# Motor_Driver.net
KiCad netlist of a schematic drawn in Altium Designer
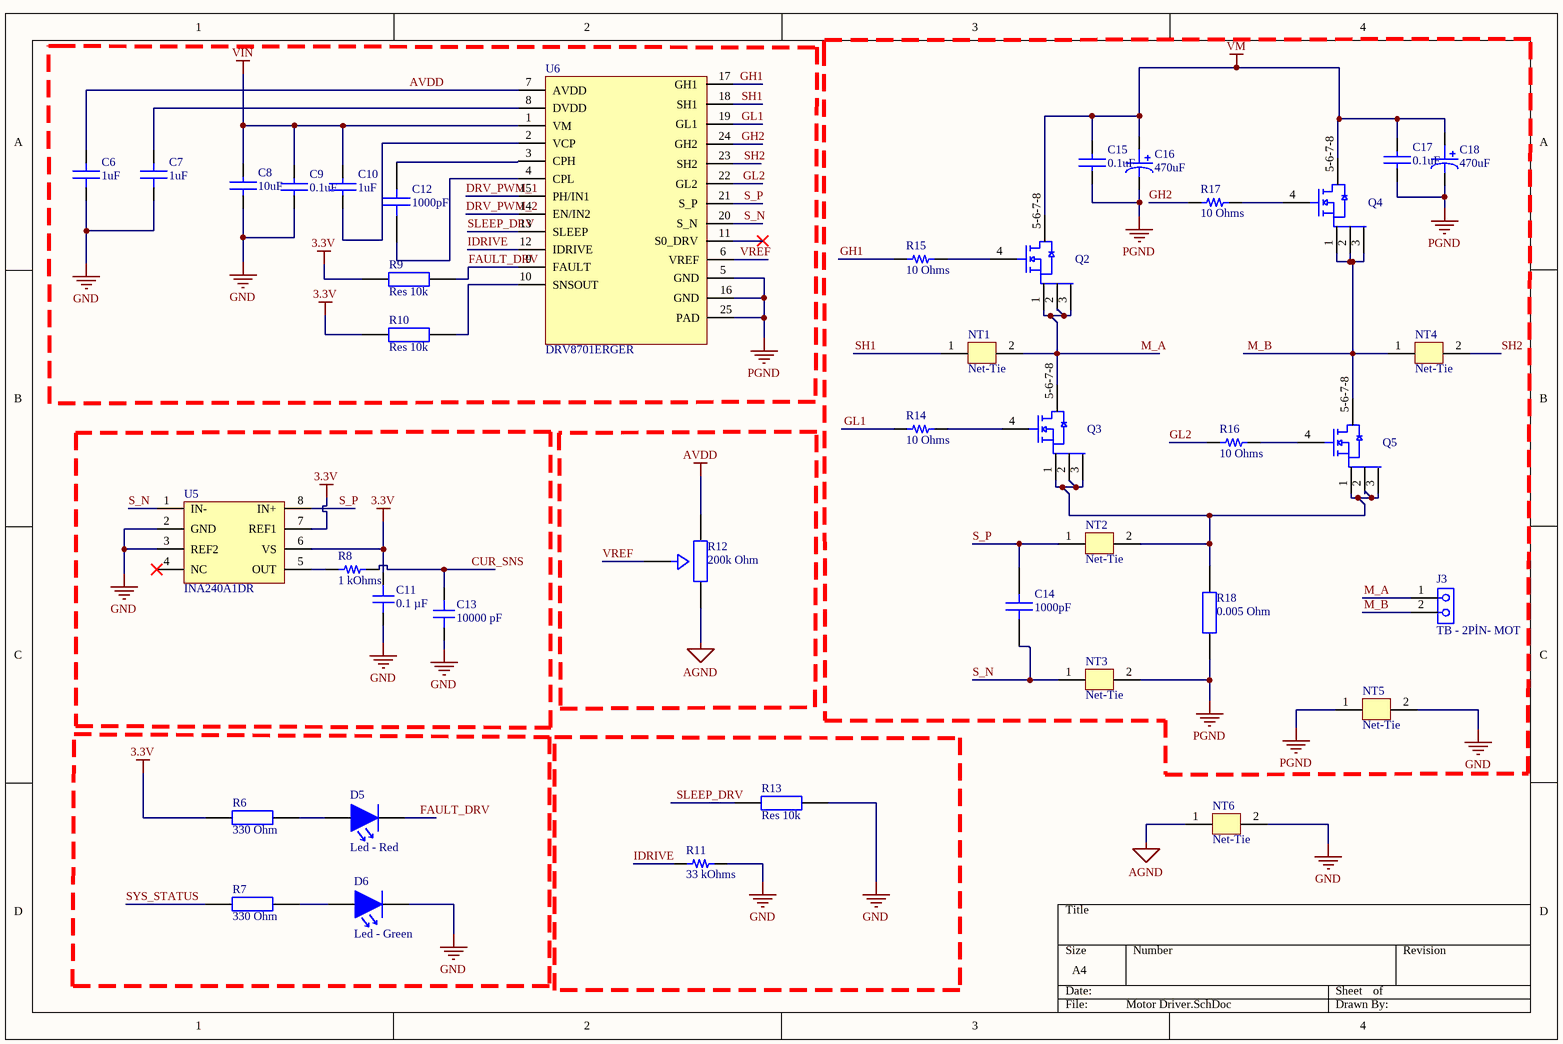
[diagram p0: Motor Driver.SchDoc]

(export (version "E")
  (design (tool "Eeschema 10.0.6"))
  (components
    (comp (ref "C6")
      (value "1uF")
      (footprint "CAP0603-GRM188R60J105KA01D")
      (description "0603 1 uF 6.3 V ±10% Tolerance X5R SMT Multilayer Ceramic Capacitor")
      (fields
        (field (name "MANUFACTURER") "Murata")
        (field (name "MANUFACTURER PART NUMBER") "GRM188R60J105KA01D")
      )
      (libsource (lib "TIDA_00620") (part "GRM188R60J105KA01D"))
    )
    (comp (ref "C7")
      (value "1uF")
      (footprint "CAP0603-GRM188R60J105KA01D")
      (description "0603 1 uF 6.3 V ±10% Tolerance X5R SMT Multilayer Ceramic Capacitor")
      (fields
        (field (name "MANUFACTURER") "Murata")
        (field (name "MANUFACTURER PART NUMBER") "GRM188R60J105KA01D")
      )
      (libsource (lib "TIDA_00620") (part "GRM188R60J105KA01D"))
    )
    (comp (ref "C8")
      (value "10uF")
      (footprint "CAP1210- GRM32ER71H106KA12L")
      (description "50V 10uF X7R ±10% 1210 Multilayer Ceramic Capacitors MLCC - SMD/SMT ROHS")
      (fields
        (field (name "MANUFACTURER") "Murata")
        (field (name "MANUFACTURER PART NUMBER") "GRM32ER71H106KA12L")
      )
      (libsource (lib "TIDA_00620") (part "GRM32ER71H106KA12L"))
    )
    (comp (ref "C9")
      (value "0.1uF")
      (footprint "CAP1206- GRM319R71H104KA01D")
      (description "1206 0.1 uF 50 V ±10 % Tolerance X7R Surface Mount Multilayer Ceramic Capacitor")
      (fields
        (field (name "MANUFACTURER") "Murata")
        (field (name "MANUFACTURER PART NUMBER") "GRM319R71H104KA01D")
      )
      (libsource (lib "TIDA_00620") (part "GRM319R71H104KA01D"))
    )
    (comp (ref "C10")
      (value "1uF")
      (footprint "CAP1206- GRM319R71C105KAA3D")
      (description "1206 1 uF 16 V ±10 % Tol. X7R Surface Mount Multilayer Ceramic Capacitor")
      (fields
        (field (name "MANUFACTURER") "Murata")
        (field (name "MANUFACTURER PART NUMBER") "GRM319R71C105KAA3D")
      )
      (libsource (lib "TIDA_00620") (part "GRM319R71C105KAA3D"))
    )
    (comp (ref "C11")
      (value "0.1 µF")
      (footprint "CAP 0603_1608")
      (description "CAP CER 0.1UF 16V X7R 0603")
      (fields
        (field (name "PART NUMBER") "AC0603KPX7R7BB104")
        (field (name "CAPACITANCE") "0.1 µF")
        (field (name "MANUFACTURER") "Yageo")
      )
      (libsource (lib "Celestial Altium Library - altium_library") (part "Capacitor"))
    )
    (comp (ref "C12")
      (value "1000pF")
      (footprint "CAP0402- GRM155R71C102KA01D")
      (description "0402 1 nF 16 V ±10% Tolerance X7R SMT Multilayer Ceramic Capacitor")
      (fields
        (field (name "MANUFACTURER") "Murata")
        (field (name "MANUFACTURER PART NUMBER") "GRM155R71C102KA01D")
      )
      (libsource (lib "") (part "GRM155R71C102KA01D_1"))
    )
    (comp (ref "C13")
      (value "10000 pF")
      (footprint "CAP 0402_1005")
      (description "CAP CER 0402 10NF 100VDC X7R")
      (fields
        (field (name "PART NUMBER") "C0402C103K1RACTU")
        (field (name "CAPACITANCE") "10000 pF")
        (field (name "MANUFACTURER") "KEMET")
      )
      (libsource (lib "Celestial Altium Library - altium_library") (part "Capacitor"))
    )
    (comp (ref "C14")
      (value "1000pF")
      (footprint "CAP0402- GRM155R71C102KA01D")
      (description "0402 1 nF 16 V ±10% Tolerance X7R SMT Multilayer Ceramic Capacitor")
      (fields
        (field (name "MANUFACTURER") "Murata")
        (field (name "MANUFACTURER PART NUMBER") "GRM155R71C102KA01D")
      )
      (libsource (lib "TIDA_00620") (part "GRM155R71C102KA01D"))
    )
    (comp (ref "C15")
      (value "0.1uF")
      (footprint "CAP1206- GRM319R71H104KA01D")
      (description "1206 0.1 uF 50 V ±10 % Tolerance X7R Surface Mount Multilayer Ceramic Capacitor")
      (fields
        (field (name "MANUFACTURER") "Murata")
        (field (name "MANUFACTURER PART NUMBER") "GRM319R71H104KA01D")
      )
      (libsource (lib "TIDA_00620") (part "GRM319R71H104KA01D"))
    )
    (comp (ref "C16")
      (value "470uF")
      (footprint "RCAP, 8x20mm -EEU-FR1V471LB")
      (description "Aluminum Electrolytic Capacitor, Polarized, Aluminum (wet), 25V, 20% +Tol, 20% -Tol, 560uF")
      (fields
        (field (name "MANUFACTURER") "Panasonic")
        (field (name "MANUFACTURER PART NUMBER") "EEU-FR1V471LB")
      )
      (libsource (lib "TIDA_00620") (part "EEU-FR1V471LB"))
    )
    (comp (ref "C17")
      (value "0.1uF")
      (footprint "CAP1206- GRM319R71H104KA01D")
      (description "1206 0.1 uF 50 V ±10 % Tolerance X7R Surface Mount Multilayer Ceramic Capacitor")
      (fields
        (field (name "MANUFACTURER") "Murata")
        (field (name "MANUFACTURER PART NUMBER") "GRM319R71H104KA01D")
      )
      (libsource (lib "TIDA_00620") (part "GRM319R71H104KA01D"))
    )
    (comp (ref "C18")
      (value "470uF")
      (footprint "RCAP, 8x20mm -EEU-FR1V471LB")
      (description "Aluminum Electrolytic Capacitor, Polarized, Aluminum (wet), 25V, 20% +Tol, 20% -Tol, 560uF")
      (fields
        (field (name "MANUFACTURER") "Panasonic")
        (field (name "MANUFACTURER PART NUMBER") "EEU-FR1V471LB")
      )
      (libsource (lib "TIDA_00620") (part "EEU-FR1V471LB"))
    )
    (comp (ref "D5")
      (value "Led - Red")
      (footprint "LED_0805")
      (description "Single-color LEDs; LITEON; LTST-C170KRKT; Red; 130 °; 2 V; 0805")
      (fields
        (field (name "MANUFACTURER") "Lite-On")
        (field (name "MANUFACTURER PART NUMBER") "LTST-C170KRKT")
        (field (name "DESIGNED") "Emre")
      )
      (libsource (lib "TIDA_00620") (part "LTST-C170KRKT"))
    )
    (comp (ref "D6")
      (value "Led - Green")
      (footprint "LED_0805")
      (description "LED Low-Power Uni-Color Green 565nm 2.1V 2-Pin Chip LED T/R")
      (fields
        (field (name "MANUFACTURER") "Lite-On")
        (field (name "MANUFACTURER PART NUMBER") "LTST-C171GKT")
        (field (name "DESIGNED") "Emre")
      )
      (libsource (lib "TIDA_00620") (part "LTST-C171GKT"))
    )
    (comp (ref "J3")
      (value "TB - 2PİN- MOT")
      (footprint "TB - 2PİN- MOT")
      (libsource (lib "TIDA_00620") (part "TB - 2PİN- MOT"))
    )
    (comp (ref "NT1") (value "Net-Tie") (footprint "Net-Tie") (libsource (lib "TIDA_00620") (part "Net-Tie")))
    (comp (ref "NT2") (value "Net-Tie") (footprint "Net-Tie") (libsource (lib "TIDA_00620") (part "Net-Tie")))
    (comp (ref "NT3") (value "Net-Tie") (footprint "Net-Tie") (libsource (lib "TIDA_00620") (part "Net-Tie")))
    (comp (ref "NT4") (value "Net-Tie") (footprint "Net-Tie") (libsource (lib "TIDA_00620") (part "Net-Tie")))
    (comp (ref "NT5") (value "Net-Tie") (footprint "Net-Tie") (libsource (lib "TIDA_00620") (part "Net-Tie")))
    (comp (ref "NT6") (value "Net-Tie") (footprint "Net-Tie") (libsource (lib "TIDA_00620") (part "Net-Tie")))
    (comp (ref "Q2")
      (value "BSC010N04LSI")
      (footprint "SON 5X6")
      (description "Transistor: N-MOSFET; unipolar; 40V; 100A; 139W; PG-TDSON-8")
      (fields
        (field (name "MANUFACTURER") "Infineon")
        (field (name "MANUFACTURER PART NUMBER") "BSC010N04LSIATMA1")
      )
      (libsource (lib "UAV") (part "BSC010N04LSI"))
    )
    (comp (ref "Q3")
      (value "BSC010N04LSI")
      (footprint "SON 5X6")
      (description "Transistor: N-MOSFET; unipolar; 40V; 100A; 139W; PG-TDSON-8")
      (fields
        (field (name "MANUFACTURER") "Infineon")
        (field (name "MANUFACTURER PART NUMBER") "BSC010N04LSIATMA1")
      )
      (libsource (lib "UAV") (part "BSC010N04LSI"))
    )
    (comp (ref "Q4")
      (value "BSC010N04LSI")
      (footprint "SON 5X6")
      (description "Transistor: N-MOSFET; unipolar; 40V; 100A; 139W; PG-TDSON-8")
      (fields
        (field (name "MANUFACTURER") "Infineon")
        (field (name "MANUFACTURER PART NUMBER") "BSC010N04LSIATMA1")
      )
      (libsource (lib "UAV") (part "BSC010N04LSI"))
    )
    (comp (ref "Q5")
      (value "BSC010N04LSI")
      (footprint "SON 5X6")
      (description "Transistor: N-MOSFET; unipolar; 40V; 100A; 139W; PG-TDSON-8")
      (fields
        (field (name "MANUFACTURER") "Infineon")
        (field (name "MANUFACTURER PART NUMBER") "BSC010N04LSIATMA1")
      )
      (libsource (lib "UAV") (part "BSC010N04LSI"))
    )
    (comp (ref "R6")
      (value "330 Ohm")
      (footprint "RES0603- RC0603FR-07330RL")
      (description "Res Thick Film 0603 330 Ohm 1% 0.1W(1/10W) ±100ppm/C Pad SMD T/R")
      (fields
        (field (name "MANUFACTURER") "Yageo Group")
        (field (name "MANUFACTURER PART NUMBER") "RC0603FR-07330RL")
      )
      (libsource (lib "TIDA_00620") (part "RC0603FR-07330RL"))
    )
    (comp (ref "R7")
      (value "330 Ohm")
      (footprint "RES0603- RC0603FR-07330RL")
      (description "Res Thick Film 0603 330 Ohm 1% 0.1W(1/10W) ±100ppm/C Pad SMD T/R")
      (fields
        (field (name "MANUFACTURER") "Yageo Group")
        (field (name "MANUFACTURER PART NUMBER") "RC0603FR-07330RL")
      )
      (libsource (lib "TIDA_00620") (part "RC0603FR-07330RL"))
    )
    (comp (ref "R8")
      (value "1 kOhms")
      (footprint "RES 0603_1608")
      (description "RES SMD 1K OHM 5% 1/4W 0603")
      (fields (field (name "PART NUMBER") "ESR03EZPJ102") (field (name "MANUFACTURER") "Rohm Semiconductor"))
      (libsource (lib "Celestial Altium Library - altium_library") (part "Resistor"))
    )
    (comp (ref "R9")
      (value "Res 10k")
      (footprint "RES0402 - ERJ-2RKF1002X")
      (description "Res Thick Film 0402 10K Ohm 1% 1/10W ±100ppm/°C Molded SMD Punched Carrier T/R")
      (fields
        (field (name "MANUFACTURER") "Panasonic")
        (field (name "MANUFACTURER PART NUMBER") "ERJ-2RKF1002X")
      )
      (libsource (lib "TIDA_00620") (part "ERJ-2RKF1002X"))
    )
    (comp (ref "R10")
      (value "Res 10k")
      (footprint "RES0402 - ERJ-2RKF1002X")
      (description "Res Thick Film 0402 10K Ohm 1% 1/10W ±100ppm/°C Molded SMD Punched Carrier T/R")
      (fields
        (field (name "MANUFACTURER") "Panasonic")
        (field (name "MANUFACTURER PART NUMBER") "ERJ-2RKF1002X")
      )
      (libsource (lib "TIDA_00620") (part "ERJ-2RKF1002X"))
    )
    (comp (ref "R11")
      (value "33 kOhms")
      (footprint "RES 1206_3216")
      (description "RES SMD 33K OHM 0.05% 1/4W 1206")
      (fields
        (field (name "PART NUMBER") "ERA-8ARW333V")
        (field (name "MANUFACTURER") "Panasonic Electronic Components")
      )
      (libsource (lib "Celestial Altium Library - altium_library") (part "Resistor"))
    )
    (comp (ref "R12")
      (value "200k Ohm")
      (footprint "3352P-1-204LF")
      (description "Res Cermet Trimmer 200K Ohm 20% 1/2W 1(Elec)/1(Mech)Turn (8.89 X 10.67 X 5.33mm) Pin Thru-Hole Bag")
      (fields
        (field (name "MANUFACTURER") "Bourns")
        (field (name "MANUFACTURER PART NUMBER") "3352P-1-204LF")
      )
      (libsource (lib "TIDA_00620") (part "3352P-1-204LF"))
    )
    (comp (ref "R13")
      (value "Res 10k")
      (footprint "RES0402 - ERJ-2RKF1002X")
      (description "Res Thick Film 0402 10K Ohm 1% 1/10W ±100ppm/°C Molded SMD Punched Carrier T/R")
      (fields
        (field (name "MANUFACTURER") "Panasonic")
        (field (name "MANUFACTURER PART NUMBER") "ERJ-2RKF1002X")
      )
      (libsource (lib "TIDA_00620") (part "ERJ-2RKF1002X"))
    )
    (comp (ref "R14")
      (value "10 Ohms")
      (footprint "RES 0805_2012")
      (description "RES SMD 10 OHM 0.5% 1/4W 0805")
      (fields
        (field (name "PART NUMBER") "RNCF0805DTE10R0")
        (field (name "MANUFACTURER") "Stackpole Electronics Inc")
      )
      (libsource (lib "Celestial Altium Library - altium_library") (part "Resistor"))
    )
    (comp (ref "R15")
      (value "10 Ohms")
      (footprint "RES 0805_2012")
      (description "RES SMD 10 OHM 0.5% 1/4W 0805")
      (fields
        (field (name "PART NUMBER") "RNCF0805DTE10R0")
        (field (name "MANUFACTURER") "Stackpole Electronics Inc")
      )
      (libsource (lib "Celestial Altium Library - altium_library") (part "Resistor"))
    )
    (comp (ref "R16")
      (value "10 Ohms")
      (footprint "RES 0805_2012")
      (description "RES SMD 10 OHM 0.5% 1/4W 0805")
      (fields
        (field (name "PART NUMBER") "RNCF0805DTE10R0")
        (field (name "MANUFACTURER") "Stackpole Electronics Inc")
      )
      (libsource (lib "Celestial Altium Library - altium_library") (part "Resistor"))
    )
    (comp (ref "R17")
      (value "10 Ohms")
      (footprint "RES 0805_2012")
      (description "RES SMD 10 OHM 0.5% 1/4W 0805")
      (fields
        (field (name "PART NUMBER") "RNCF0805DTE10R0")
        (field (name "MANUFACTURER") "Stackpole Electronics Inc")
      )
      (libsource (lib "Celestial Altium Library - altium_library") (part "Resistor"))
    )
    (comp (ref "R18")
      (value "0.005 Ohm")
      (footprint "KRL11050-C-R005-F-T1")
      (description "Fixed Resistor, Metal Foil, 5W, 0.005ohm, 1% +/-Tol, 50ppm/Cel, Surface Mount, 4320")
      (fields
        (field (name "MANUFACTURER") "Susumu")
        (field (name "MANUFACTURER PART NUMBER") "KRL11050-C-R005-F-T1")
      )
      (libsource (lib "TIDA_00620") (part "KRL11050-C-R005-F-T1"))
    )
    (comp (ref "U5")
      (value "INA240A1DR")
      (footprint "INA240A1DR")
      (description "Op Amp Single Zero Drift Amplifier 5.5V 8-Pin SOIC T/R")
      (fields (field (name "MANUFACTURER") "Texas Instruments"))
      (libsource (lib "TIDA_00620") (part "INA240A1DR"))
    )
    (comp (ref "U6")
      (value "DRV8701ERGER")
      (footprint "DRV8701ERGER")
      (description "IC MOTOR DRIVER 0V-5.5V 24VQFN / DRV8701 Brushed DC Motor Full-Bridge Gate Driver")
      (fields (field (name "MANUFACTURER") "Texas Instruments"))
      (libsource (lib "TIDA_00620") (part "DRV8701ERGER"))
    )
  )
  (nets
    (net (code "1") (name "/CUR_SNS") (class "Default")
      (node (ref "C13") (pin "2") (pinfunction "2_2") (pintype "passive"))
      (node (ref "R8") (pin "2") (pinfunction "2_2") (pintype "passive"))
    )
    (net (code "2") (name "/DRV_PWM_1") (class "Default")
      (node (ref "U6") (pin "15") (pinfunction "PH/IN1_15") (pintype "passive"))
    )
    (net (code "3") (name "/DRV_PWM_2") (class "Default")
      (node (ref "U6") (pin "14") (pinfunction "EN/IN2_14") (pintype "passive"))
    )
    (net (code "4") (name "/FAULT_DRV") (class "Default")
      (node (ref "D5") (pin "1") (pinfunction "1_1") (pintype "power_in"))
      (node (ref "R9") (pin "2") (pinfunction "2_2") (pintype "passive"))
      (node (ref "U6") (pin "9") (pinfunction "FAULT_9") (pintype "passive"))
    )
    (net (code "5") (name "/GH1") (class "Default")
      (node (ref "R15") (pin "1") (pinfunction "1_1") (pintype "passive"))
      (node (ref "U6") (pin "17") (pinfunction "GH1_17") (pintype "passive"))
    )
    (net (code "6") (name "/GH2") (class "Default")
      (node (ref "R17") (pin "1") (pinfunction "1_1") (pintype "passive"))
      (node (ref "U6") (pin "24") (pinfunction "GH2_24") (pintype "passive"))
    )
    (net (code "7") (name "/GL1") (class "Default")
      (node (ref "R14") (pin "1") (pinfunction "1_1") (pintype "passive"))
      (node (ref "U6") (pin "19") (pinfunction "GL1_19") (pintype "passive"))
    )
    (net (code "8") (name "/GL2") (class "Default")
      (node (ref "R16") (pin "1") (pinfunction "1_1") (pintype "passive"))
      (node (ref "U6") (pin "22") (pinfunction "GL2_22") (pintype "passive"))
    )
    (net (code "9") (name "/IDRIVE") (class "Default")
      (node (ref "R11") (pin "2") (pinfunction "2_2") (pintype "passive"))
      (node (ref "U6") (pin "12") (pinfunction "IDRIVE_12") (pintype "passive"))
    )
    (net (code "10") (name "/M_A") (class "Default")
      (node (ref "J3") (pin "1") (pinfunction "1_1") (pintype "passive"))
      (node (ref "NT1") (pin "2") (pinfunction "2_2") (pintype "passive"))
      (node (ref "Q2") (pin "1") (pinfunction "S_1") (pintype "passive"))
      (node (ref "Q2") (pin "2") (pinfunction "S_2") (pintype "passive"))
      (node (ref "Q2") (pin "3") (pinfunction "S_3") (pintype "passive"))
      (node (ref "Q3") (pin "5-6-7-8") (pinfunction "D_5-6-7-8") (pintype "passive"))
    )
    (net (code "11") (name "/M_B") (class "Default")
      (node (ref "J3") (pin "2") (pinfunction "2_2") (pintype "passive"))
      (node (ref "NT4") (pin "1") (pinfunction "1_1") (pintype "passive"))
      (node (ref "Q4") (pin "1") (pinfunction "S_1") (pintype "passive"))
      (node (ref "Q4") (pin "2") (pinfunction "S_2") (pintype "passive"))
      (node (ref "Q4") (pin "3") (pinfunction "S_3") (pintype "passive"))
      (node (ref "Q5") (pin "5-6-7-8") (pinfunction "D_5-6-7-8") (pintype "passive"))
    )
    (net (code "12") (name "/SH1") (class "Default")
      (node (ref "NT1") (pin "1") (pinfunction "1_1") (pintype "passive"))
      (node (ref "U6") (pin "18") (pinfunction "SH1_18") (pintype "passive"))
    )
    (net (code "13") (name "/SH2") (class "Default")
      (node (ref "NT4") (pin "2") (pinfunction "2_2") (pintype "passive"))
      (node (ref "U6") (pin "23") (pinfunction "SH2_23") (pintype "passive"))
    )
    (net (code "14") (name "/SLEEP_DRV") (class "Default")
      (node (ref "R13") (pin "1") (pinfunction "1_1") (pintype "passive"))
      (node (ref "U6") (pin "13") (pinfunction "SLEEP_13") (pintype "passive"))
    )
    (net (code "15") (name "/SYS_STATUS") (class "Default")
      (node (ref "R7") (pin "1") (pinfunction "1_1") (pintype "passive"))
    )
    (net (code "16") (name "/S_N") (class "Default")
      (node (ref "C14") (pin "1") (pinfunction "1_1") (pintype "passive"))
      (node (ref "NT3") (pin "1") (pinfunction "1_1") (pintype "passive"))
      (node (ref "U5") (pin "1") (pinfunction "IN-_1") (pintype "passive"))
      (node (ref "U6") (pin "20") (pinfunction "S_N_20") (pintype "passive"))
    )
    (net (code "17") (name "/S_P") (class "Default")
      (node (ref "C14") (pin "2") (pinfunction "2_2") (pintype "passive"))
      (node (ref "NT2") (pin "1") (pinfunction "1_1") (pintype "passive"))
      (node (ref "U5") (pin "8") (pinfunction "IN+_8") (pintype "passive"))
      (node (ref "U6") (pin "21") (pinfunction "S_P_21") (pintype "passive"))
    )
    (net (code "18") (name "/VREF") (class "Default")
      (node (ref "R12") (pin "1") (pinfunction "1_1") (pintype "passive"))
      (node (ref "U6") (pin "6") (pinfunction "VREF_6") (pintype "passive"))
    )
    (net (code "19") (name "3.3V") (class "Default")
      (node (ref "C11") (pin "2") (pinfunction "2_2") (pintype "passive"))
      (node (ref "R10") (pin "1") (pinfunction "1_1") (pintype "passive"))
      (node (ref "R6") (pin "1") (pinfunction "1_1") (pintype "passive"))
      (node (ref "R9") (pin "1") (pinfunction "1_1") (pintype "passive"))
      (node (ref "U5") (pin "6") (pinfunction "VS_6") (pintype "passive"))
      (node (ref "U5") (pin "7") (pinfunction "REF1_7") (pintype "passive"))
    )
    (net (code "20") (name "AGND") (class "Default")
      (node (ref "NT6") (pin "1") (pinfunction "1_1") (pintype "passive"))
      (node (ref "R12") (pin "3") (pinfunction "3_3") (pintype "passive"))
    )
    (net (code "21") (name "AVDD") (class "Default")
      (node (ref "C6") (pin "2") (pinfunction "2_2") (pintype "passive"))
      (node (ref "R12") (pin "2") (pinfunction "2_2") (pintype "passive"))
      (node (ref "U6") (pin "7") (pinfunction "AVDD_7") (pintype "passive"))
    )
    (net (code "22") (name "GND") (class "Default")
      (node (ref "C11") (pin "1") (pinfunction "1_1") (pintype "passive"))
      (node (ref "C13") (pin "1") (pinfunction "1_1") (pintype "passive"))
      (node (ref "C6") (pin "1") (pinfunction "1_1") (pintype "passive"))
      (node (ref "C7") (pin "1") (pinfunction "1_1") (pintype "passive"))
      (node (ref "C8") (pin "1") (pinfunction "1_1") (pintype "passive"))
      (node (ref "C9") (pin "1") (pinfunction "1_1") (pintype "passive"))
      (node (ref "D6") (pin "1") (pinfunction "1_1") (pintype "power_in"))
      (node (ref "NT5") (pin "2") (pinfunction "2_2") (pintype "passive"))
      (node (ref "NT6") (pin "2") (pinfunction "2_2") (pintype "passive"))
      (node (ref "R11") (pin "1") (pinfunction "1_1") (pintype "passive"))
      (node (ref "R13") (pin "2") (pinfunction "2_2") (pintype "passive"))
      (node (ref "U5") (pin "2") (pinfunction "GND_2") (pintype "passive"))
      (node (ref "U5") (pin "3") (pinfunction "REF2_3") (pintype "passive"))
    )
    (net (code "23") (name "Net-(D5-Pad2)") (class "Default")
      (node (ref "D5") (pin "2") (pinfunction "2_2") (pintype "power_in"))
      (node (ref "R6") (pin "2") (pinfunction "2_2") (pintype "passive"))
    )
    (net (code "24") (name "Net-(D6-Pad2)") (class "Default")
      (node (ref "D6") (pin "2") (pinfunction "2_2") (pintype "power_in"))
      (node (ref "R7") (pin "2") (pinfunction "2_2") (pintype "passive"))
    )
    (net (code "25") (name "Net-(NT2-Pad2)") (class "Default")
      (node (ref "NT2") (pin "2") (pinfunction "2_2") (pintype "passive"))
      (node (ref "Q3") (pin "1") (pinfunction "S_1") (pintype "passive"))
      (node (ref "Q3") (pin "2") (pinfunction "S_2") (pintype "passive"))
      (node (ref "Q3") (pin "3") (pinfunction "S_3") (pintype "passive"))
      (node (ref "Q5") (pin "1") (pinfunction "S_1") (pintype "passive"))
      (node (ref "Q5") (pin "2") (pinfunction "S_2") (pintype "passive"))
      (node (ref "Q5") (pin "3") (pinfunction "S_3") (pintype "passive"))
      (node (ref "R18") (pin "2") (pinfunction "2_2") (pintype "passive"))
    )
    (net (code "26") (name "Net-(Q2-G)") (class "Default")
      (node (ref "Q2") (pin "4") (pinfunction "G_4") (pintype "passive"))
      (node (ref "R15") (pin "2") (pinfunction "2_2") (pintype "passive"))
    )
    (net (code "27") (name "Net-(Q3-G)") (class "Default")
      (node (ref "Q3") (pin "4") (pinfunction "G_4") (pintype "passive"))
      (node (ref "R14") (pin "2") (pinfunction "2_2") (pintype "passive"))
    )
    (net (code "28") (name "Net-(Q4-G)") (class "Default")
      (node (ref "Q4") (pin "4") (pinfunction "G_4") (pintype "passive"))
      (node (ref "R17") (pin "2") (pinfunction "2_2") (pintype "passive"))
    )
    (net (code "29") (name "Net-(Q5-G)") (class "Default")
      (node (ref "Q5") (pin "4") (pinfunction "G_4") (pintype "passive"))
      (node (ref "R16") (pin "2") (pinfunction "2_2") (pintype "passive"))
    )
    (net (code "30") (name "Net-(U5-OUT)") (class "Default")
      (node (ref "R8") (pin "1") (pinfunction "1_1") (pintype "passive"))
      (node (ref "U5") (pin "5") (pinfunction "OUT_5") (pintype "passive"))
    )
    (net (code "31") (name "Net-(U6-CPH)") (class "Default")
      (node (ref "C12") (pin "2") (pinfunction "2_2") (pintype "passive"))
      (node (ref "U6") (pin "3") (pinfunction "CPH_3") (pintype "passive"))
    )
    (net (code "32") (name "Net-(U6-CPL)") (class "Default")
      (node (ref "C12") (pin "1") (pinfunction "1_1") (pintype "passive"))
      (node (ref "U6") (pin "4") (pinfunction "CPL_4") (pintype "passive"))
    )
    (net (code "33") (name "Net-(U6-DVDD)") (class "Default")
      (node (ref "C7") (pin "2") (pinfunction "2_2") (pintype "passive"))
      (node (ref "U6") (pin "8") (pinfunction "DVDD_8") (pintype "passive"))
    )
    (net (code "34") (name "Net-(U6-SNSOUT)") (class "Default")
      (node (ref "R10") (pin "2") (pinfunction "2_2") (pintype "passive"))
      (node (ref "U6") (pin "10") (pinfunction "SNSOUT_10") (pintype "passive"))
    )
    (net (code "35") (name "Net-(U6-VCP)") (class "Default")
      (node (ref "C10") (pin "1") (pinfunction "1_1") (pintype "passive"))
      (node (ref "U6") (pin "2") (pinfunction "VCP_2") (pintype "power_in"))
    )
    (net (code "36") (name "PGND") (class "Default")
      (node (ref "C15") (pin "1") (pinfunction "1_1") (pintype "passive"))
      (node (ref "C16") (pin "N") (pinfunction "2_N") (pintype "passive"))
      (node (ref "C17") (pin "1") (pinfunction "1_1") (pintype "passive"))
      (node (ref "C18") (pin "N") (pinfunction "2_N") (pintype "passive"))
      (node (ref "NT3") (pin "2") (pinfunction "2_2") (pintype "passive"))
      (node (ref "NT5") (pin "1") (pinfunction "1_1") (pintype "passive"))
      (node (ref "R18") (pin "1") (pinfunction "1_1") (pintype "passive"))
      (node (ref "U6") (pin "16") (pinfunction "GND_16") (pintype "power_in"))
      (node (ref "U6") (pin "25") (pinfunction "PAD_25") (pintype "power_in"))
      (node (ref "U6") (pin "5") (pinfunction "GND_5") (pintype "power_in"))
    )
    (net (code "37") (name "VIN") (class "Default")
      (node (ref "C10") (pin "2") (pinfunction "2_2") (pintype "passive"))
      (node (ref "C8") (pin "2") (pinfunction "2_2") (pintype "passive"))
      (node (ref "C9") (pin "2") (pinfunction "2_2") (pintype "passive"))
      (node (ref "U6") (pin "1") (pinfunction "VM_1") (pintype "power_in"))
    )
    (net (code "38") (name "VM") (class "Default")
      (node (ref "C15") (pin "2") (pinfunction "2_2") (pintype "passive"))
      (node (ref "C16") (pin "P") (pinfunction "1_P") (pintype "passive"))
      (node (ref "C17") (pin "2") (pinfunction "2_2") (pintype "passive"))
      (node (ref "C18") (pin "P") (pinfunction "1_P") (pintype "passive"))
      (node (ref "Q2") (pin "5-6-7-8") (pinfunction "D_5-6-7-8") (pintype "passive"))
      (node (ref "Q4") (pin "5-6-7-8") (pinfunction "D_5-6-7-8") (pintype "passive"))
    )
    (net (code "39") (name "unconnected-(U5-NC-Pad4)") (class "Default")
      (node (ref "U5") (pin "4") (pinfunction "NC_4") (pintype "passive+no_connect"))
    )
    (net (code "40") (name "unconnected-(U6-S0_DRV-Pad11)") (class "Default")
      (node (ref "U6") (pin "11") (pinfunction "S0_DRV_11") (pintype "passive+no_connect"))
    )
  )
)
